# JacdacBreadboardConnectorEc30_131.net
KiCad netlist of a schematic drawn in Altium Designer
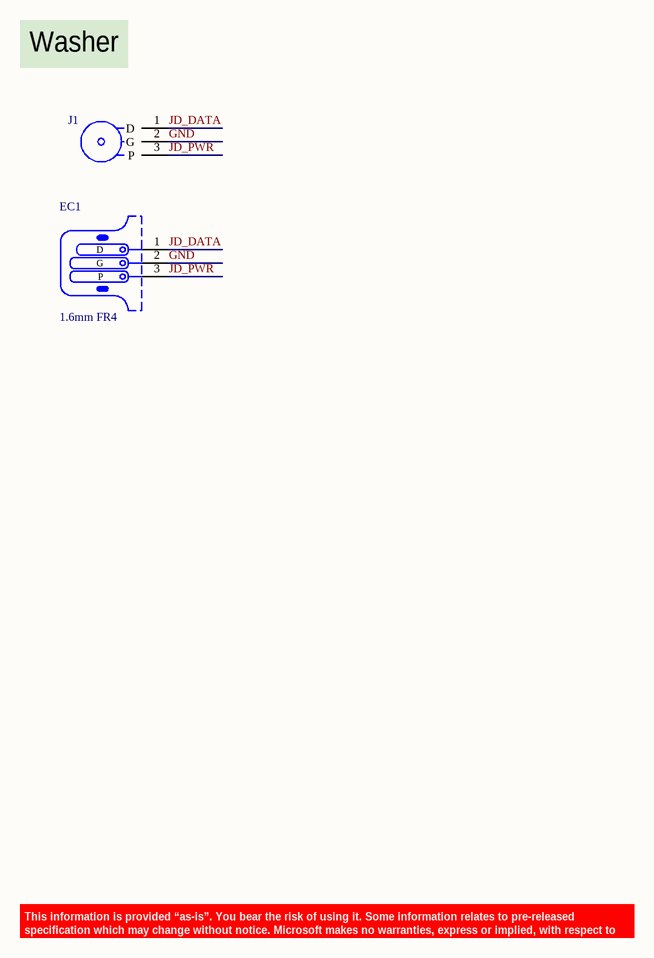
[diagram p0: JacdacBreadboardConnectorEc30 131.SchDoc]

(export (version "E")
  (design (tool "Eeschema 10.0.6"))
  (components
    (comp (ref "EC1")
      (value "Jacdac edge connector")
      (footprint "JACDAC_edge_connector:JACDAC_EDGE_CONNECTOR_NO_TRACES_3D_PADS")
      (description "3 pin Jacdac edge connector 1.27mm pitch")
      (fields
        (field (name "MANUFACTURER PART NUMBER") "n/a")
        (field (name "PCB TYPE") "1.6mm FR4")
        (field (name "CREATED BY") "D. Gakure & S. Hodges")
      )
      (libsource (lib "generic-con") (part "Jacdac edge connector"))
    )
    (comp (ref "J1")
      (value "Jacdac breadboard washer all signals")
      (footprint "Jacdac_misc:Jacdac_breadboard_transition_hole_rings_allpins")
      (libsource (lib "generic-con") (part "Jacdac breadboard washer all signals"))
    )
  )
  (nets
    (net (code "1") (name "/GND") (class "Default")
      (node (ref "EC1") (pin "2") (pinfunction "G_2") (pintype "passive"))
      (node (ref "J1") (pin "2") (pinfunction "G_2") (pintype "passive"))
    )
    (net (code "2") (name "/JD_DATA") (class "Default")
      (node (ref "EC1") (pin "1") (pinfunction "D_1") (pintype "passive"))
      (node (ref "J1") (pin "1") (pinfunction "D_1") (pintype "passive"))
    )
    (net (code "3") (name "/JD_PWR") (class "Default")
      (node (ref "EC1") (pin "3") (pinfunction "P_3") (pintype "passive"))
      (node (ref "J1") (pin "3") (pinfunction "P_3") (pintype "passive"))
    )
  )
)
